# 32-085.net
KiCad netlist of a schematic drawn in Altium Designer
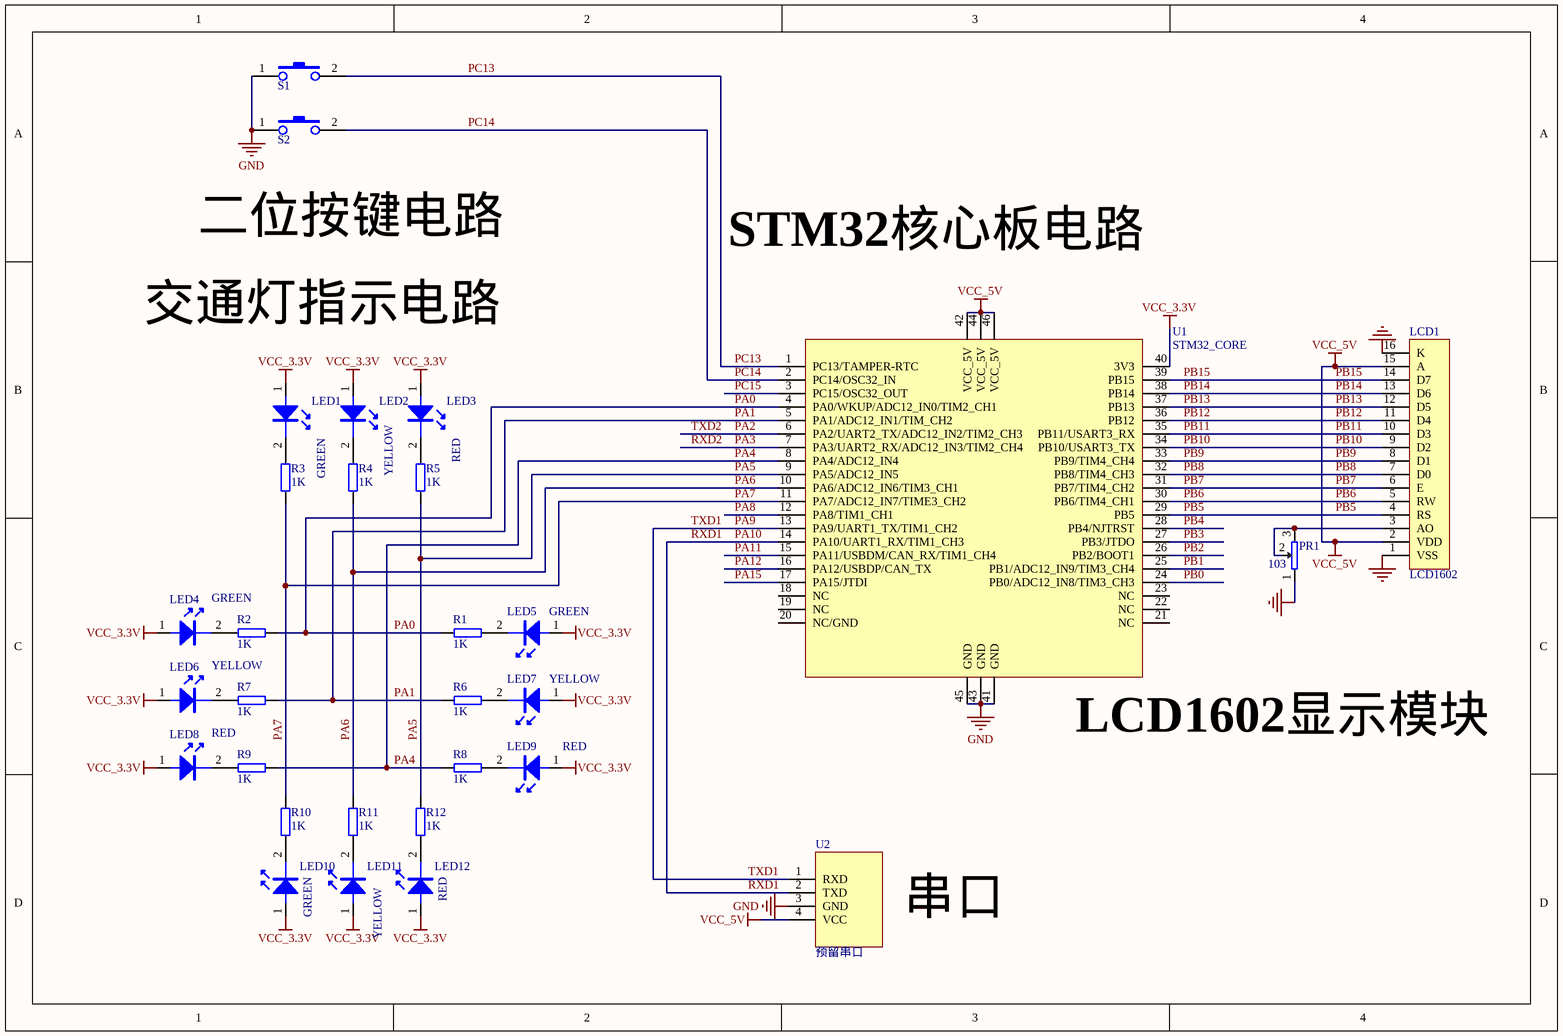
[diagram p0: 32-085原理图（源文件格式）.SchDoc]

(export (version "E")
  (design (tool "Eeschema 10.0.6"))
  (components
    (comp (ref "LCD1")
      (value "LCD1602")
      (footprint "LCD1602")
      (description "LCD1602液晶")
      (libsource (lib "参考") (part "LCD1602"))
    )
    (comp (ref "LED1")
      (value "GREEN")
      (footprint "LED_D3MM12")
      (description "LED灯")
      (libsource (lib "参考") (part "LED"))
    )
    (comp (ref "LED2")
      (value "YELLOW")
      (footprint "LED_D3MM12")
      (description "LED灯")
      (libsource (lib "参考") (part "LED"))
    )
    (comp (ref "LED3")
      (value "RED")
      (footprint "LED_D3MM12")
      (description "LED灯")
      (libsource (lib "参考") (part "LED"))
    )
    (comp (ref "LED4")
      (value "GREEN")
      (footprint "LED_D3MM12")
      (description "LED灯")
      (libsource (lib "参考") (part "LED"))
    )
    (comp (ref "LED5")
      (value "GREEN")
      (footprint "LED_D3MM12")
      (description "LED灯")
      (libsource (lib "参考") (part "LED"))
    )
    (comp (ref "LED6")
      (value "YELLOW")
      (footprint "LED_D3MM12")
      (description "LED灯")
      (libsource (lib "参考") (part "LED"))
    )
    (comp (ref "LED7")
      (value "YELLOW")
      (footprint "LED_D3MM12")
      (description "LED灯")
      (libsource (lib "参考") (part "LED"))
    )
    (comp (ref "LED8")
      (value "RED")
      (footprint "LED_D3MM12")
      (description "LED灯")
      (libsource (lib "参考") (part "LED"))
    )
    (comp (ref "LED9")
      (value "RED")
      (footprint "LED_D3MM12")
      (description "LED灯")
      (libsource (lib "参考") (part "LED"))
    )
    (comp (ref "LED10")
      (value "GREEN")
      (footprint "LED_D3MM12")
      (description "LED灯")
      (libsource (lib "参考") (part "LED"))
    )
    (comp (ref "LED11")
      (value "YELLOW")
      (footprint "LED_D3MM12")
      (description "LED灯")
      (libsource (lib "参考") (part "LED"))
    )
    (comp (ref "LED12")
      (value "RED")
      (footprint "LED_D3MM12")
      (description "LED灯")
      (libsource (lib "参考") (part "LED"))
    )
    (comp (ref "PR1")
      (value "103")
      (footprint "WH06-2")
      (description "电位器")
      (libsource (lib "参考") (part "PR"))
    )
    (comp (ref "R1")
      (value "1K")
      (footprint "AXIAL0.4")
      (description "电阻")
      (libsource (lib "参考") (part "RES"))
    )
    (comp (ref "R2")
      (value "1K")
      (footprint "AXIAL0.3")
      (description "电阻")
      (libsource (lib "参考") (part "RES"))
    )
    (comp (ref "R3")
      (value "1K")
      (footprint "AXIAL0.3")
      (description "电阻")
      (libsource (lib "参考") (part "RES"))
    )
    (comp (ref "R4")
      (value "1K")
      (footprint "AXIAL0.3")
      (description "电阻")
      (libsource (lib "参考") (part "RES"))
    )
    (comp (ref "R5")
      (value "1K")
      (footprint "AXIAL0.3")
      (description "电阻")
      (libsource (lib "参考") (part "RES"))
    )
    (comp (ref "R6")
      (value "1K")
      (footprint "AXIAL0.4")
      (description "电阻")
      (libsource (lib "参考") (part "RES"))
    )
    (comp (ref "R7")
      (value "1K")
      (footprint "AXIAL0.3")
      (description "电阻")
      (libsource (lib "参考") (part "RES"))
    )
    (comp (ref "R8")
      (value "1K")
      (footprint "AXIAL0.4")
      (description "电阻")
      (libsource (lib "参考") (part "RES"))
    )
    (comp (ref "R9")
      (value "1K")
      (footprint "AXIAL0.3")
      (description "电阻")
      (libsource (lib "参考") (part "RES"))
    )
    (comp (ref "R10")
      (value "1K")
      (footprint "AXIAL0.3")
      (description "电阻")
      (libsource (lib "参考") (part "RES"))
    )
    (comp (ref "R11")
      (value "1K")
      (footprint "AXIAL0.3")
      (description "电阻")
      (libsource (lib "参考") (part "RES"))
    )
    (comp (ref "R12")
      (value "1K")
      (footprint "AXIAL0.3")
      (description "电阻")
      (libsource (lib "参考") (part "RES"))
    )
    (comp (ref "S1")
      (value "BUTTOM")
      (footprint "BUTTOM_6x6DIP")
      (description "按键")
      (libsource (lib "参考") (part "BUTTOM"))
    )
    (comp (ref "S2")
      (value "BUTTOM")
      (footprint "BUTTOM_6x6DIP")
      (description "按键")
      (libsource (lib "参考") (part "BUTTOM"))
    )
    (comp (ref "U1")
      (value "STM32_CORE")
      (footprint "STM32_CORE")
      (description "STM32核心板")
      (libsource (lib "参考") (part "STM32_CORE"))
    )
    (comp (ref "U2") (value "预留串口") (footprint "蓝牙MODE竖放") (libsource (lib "参考") (part "蓝牙MODE")))
  )
  (nets
    (net (code "1") (name "/PA0") (class "Default")
      (node (ref "R1") (pin "1") (pinfunction "1_1") (pintype "passive"))
      (node (ref "R2") (pin "1") (pinfunction "1_1") (pintype "passive"))
      (node (ref "U1") (pin "4") (pinfunction "PA0/WKUP/ADC12_IN0/TIM2_CH1_4") (pintype "passive"))
    )
    (net (code "2") (name "/PA1") (class "Default")
      (node (ref "R6") (pin "1") (pinfunction "1_1") (pintype "passive"))
      (node (ref "R7") (pin "1") (pinfunction "1_1") (pintype "passive"))
      (node (ref "U1") (pin "5") (pinfunction "PA1/ADC12_IN1/TIM_CH2_5") (pintype "passive"))
    )
    (net (code "3") (name "/PA2") (class "Default")
      (node (ref "U1") (pin "6") (pinfunction "PA2/UART2_TX/ADC12_IN2/TIM2_CH3_6") (pintype "passive"))
    )
    (net (code "4") (name "/PA3") (class "Default")
      (node (ref "U1") (pin "7") (pinfunction "PA3/UART2_RX/ADC12_IN3/TIM2_CH4_7") (pintype "passive"))
    )
    (net (code "5") (name "/PA4") (class "Default")
      (node (ref "R8") (pin "1") (pinfunction "1_1") (pintype "passive"))
      (node (ref "R9") (pin "1") (pinfunction "1_1") (pintype "passive"))
      (node (ref "U1") (pin "8") (pinfunction "PA4/ADC12_IN4_8") (pintype "passive"))
    )
    (net (code "6") (name "/PA5") (class "Default")
      (node (ref "R12") (pin "1") (pinfunction "1_1") (pintype "passive"))
      (node (ref "R5") (pin "1") (pinfunction "1_1") (pintype "passive"))
      (node (ref "U1") (pin "9") (pinfunction "PA5/ADC12_IN5_9") (pintype "passive"))
    )
    (net (code "7") (name "/PA6") (class "Default")
      (node (ref "R11") (pin "1") (pinfunction "1_1") (pintype "passive"))
      (node (ref "R4") (pin "1") (pinfunction "1_1") (pintype "passive"))
      (node (ref "U1") (pin "10") (pinfunction "PA6/ADC12_IN6/TIM3_CH1_10") (pintype "passive"))
    )
    (net (code "8") (name "/PA7") (class "Default")
      (node (ref "R10") (pin "1") (pinfunction "1_1") (pintype "passive"))
      (node (ref "R3") (pin "1") (pinfunction "1_1") (pintype "passive"))
      (node (ref "U1") (pin "11") (pinfunction "PA7/ADC12_IN7/TIME3_CH2_11") (pintype "passive"))
    )
    (net (code "9") (name "/PA8") (class "Default")
      (node (ref "U1") (pin "12") (pinfunction "PA8/TIM1_CH1_12") (pintype "passive"))
    )
    (net (code "10") (name "/PA9") (class "Default")
      (node (ref "U1") (pin "13") (pinfunction "PA9/UART1_TX/TIM1_CH2_13") (pintype "passive"))
      (node (ref "U2") (pin "1") (pinfunction "RXD_1") (pintype "passive"))
    )
    (net (code "11") (name "/PA10") (class "Default")
      (node (ref "U1") (pin "14") (pinfunction "PA10/UART1_RX/TIM1_CH3_14") (pintype "passive"))
      (node (ref "U2") (pin "2") (pinfunction "TXD_2") (pintype "passive"))
    )
    (net (code "12") (name "/PA11") (class "Default")
      (node (ref "U1") (pin "15") (pinfunction "PA11/USBDM/CAN_RX/TIM1_CH4_15") (pintype "passive"))
    )
    (net (code "13") (name "/PA12") (class "Default")
      (node (ref "U1") (pin "16") (pinfunction "PA12/USBDP/CAN_TX_16") (pintype "passive"))
    )
    (net (code "14") (name "/PA15") (class "Default")
      (node (ref "U1") (pin "17") (pinfunction "PA15/JTDI_17") (pintype "passive"))
    )
    (net (code "15") (name "/PB0") (class "Default")
      (node (ref "U1") (pin "24") (pinfunction "PB0/ADC12_IN8/TIM3_CH3_24") (pintype "passive"))
    )
    (net (code "16") (name "/PB1") (class "Default")
      (node (ref "U1") (pin "25") (pinfunction "PB1/ADC12_IN9/TIM3_CH4_25") (pintype "passive"))
    )
    (net (code "17") (name "/PB2") (class "Default")
      (node (ref "U1") (pin "26") (pinfunction "PB2/BOOT1_26") (pintype "passive"))
    )
    (net (code "18") (name "/PB3") (class "Default")
      (node (ref "U1") (pin "27") (pinfunction "PB3/JTDO_27") (pintype "passive"))
    )
    (net (code "19") (name "/PB4") (class "Default")
      (node (ref "U1") (pin "28") (pinfunction "PB4/NJTRST_28") (pintype "passive"))
    )
    (net (code "20") (name "/PB5") (class "Default")
      (node (ref "LCD1") (pin "4") (pinfunction "RS_4") (pintype "passive"))
      (node (ref "U1") (pin "29") (pinfunction "PB5_29") (pintype "passive"))
    )
    (net (code "21") (name "/PB6") (class "Default")
      (node (ref "LCD1") (pin "5") (pinfunction "RW_5") (pintype "passive"))
      (node (ref "U1") (pin "30") (pinfunction "PB6/TIM4_CH1_30") (pintype "passive"))
    )
    (net (code "22") (name "/PB7") (class "Default")
      (node (ref "LCD1") (pin "6") (pinfunction "E_6") (pintype "passive"))
      (node (ref "U1") (pin "31") (pinfunction "PB7/TIM4_CH2_31") (pintype "passive"))
    )
    (net (code "23") (name "/PB8") (class "Default")
      (node (ref "LCD1") (pin "7") (pinfunction "D0_7") (pintype "passive"))
      (node (ref "U1") (pin "32") (pinfunction "PB8/TIM4_CH3_32") (pintype "passive"))
    )
    (net (code "24") (name "/PB9") (class "Default")
      (node (ref "LCD1") (pin "8") (pinfunction "D1_8") (pintype "passive"))
      (node (ref "U1") (pin "33") (pinfunction "PB9/TIM4_CH4_33") (pintype "passive"))
    )
    (net (code "25") (name "/PB10") (class "Default")
      (node (ref "LCD1") (pin "9") (pinfunction "D2_9") (pintype "passive"))
      (node (ref "U1") (pin "34") (pinfunction "PB10/USART3_TX_34") (pintype "passive"))
    )
    (net (code "26") (name "/PB11") (class "Default")
      (node (ref "LCD1") (pin "10") (pinfunction "D3_10") (pintype "passive"))
      (node (ref "U1") (pin "35") (pinfunction "PB11/USART3_RX_35") (pintype "passive"))
    )
    (net (code "27") (name "/PB12") (class "Default")
      (node (ref "LCD1") (pin "11") (pinfunction "D4_11") (pintype "passive"))
      (node (ref "U1") (pin "36") (pinfunction "PB12_36") (pintype "passive"))
    )
    (net (code "28") (name "/PB13") (class "Default")
      (node (ref "LCD1") (pin "12") (pinfunction "D5_12") (pintype "passive"))
      (node (ref "U1") (pin "37") (pinfunction "PB13_37") (pintype "passive"))
    )
    (net (code "29") (name "/PB14") (class "Default")
      (node (ref "LCD1") (pin "13") (pinfunction "D6_13") (pintype "passive"))
      (node (ref "U1") (pin "38") (pinfunction "PB14_38") (pintype "passive"))
    )
    (net (code "30") (name "/PB15") (class "Default")
      (node (ref "LCD1") (pin "14") (pinfunction "D7_14") (pintype "passive"))
      (node (ref "U1") (pin "39") (pinfunction "PB15_39") (pintype "passive"))
    )
    (net (code "31") (name "/PC13") (class "Default")
      (node (ref "S1") (pin "2") (pinfunction "2_2") (pintype "passive"))
      (node (ref "U1") (pin "1") (pinfunction "PC13/TAMPER-RTC_1") (pintype "passive"))
    )
    (net (code "32") (name "/PC14") (class "Default")
      (node (ref "S2") (pin "2") (pinfunction "2_2") (pintype "passive"))
      (node (ref "U1") (pin "2") (pinfunction "PC14/OSC32_IN_2") (pintype "passive"))
    )
    (net (code "33") (name "/PC15") (class "Default")
      (node (ref "U1") (pin "3") (pinfunction "PC15/OSC32_OUT_3") (pintype "passive"))
    )
    (net (code "34") (name "GND") (class "Default")
      (node (ref "LCD1") (pin "1") (pinfunction "VSS_1") (pintype "passive"))
      (node (ref "LCD1") (pin "16") (pinfunction "K_16") (pintype "passive"))
      (node (ref "PR1") (pin "1") (pinfunction "1_1") (pintype "passive"))
      (node (ref "S1") (pin "1") (pinfunction "1_1") (pintype "passive"))
      (node (ref "S2") (pin "1") (pinfunction "1_1") (pintype "passive"))
      (node (ref "U1") (pin "41") (pinfunction "GND_41") (pintype "passive"))
      (node (ref "U1") (pin "43") (pinfunction "GND_43") (pintype "passive"))
      (node (ref "U1") (pin "45") (pinfunction "GND_45") (pintype "passive"))
      (node (ref "U2") (pin "3") (pinfunction "GND_3") (pintype "passive"))
    )
    (net (code "35") (name "Net-(LCD1-AO)") (class "Default")
      (node (ref "LCD1") (pin "3") (pinfunction "AO_3") (pintype "passive"))
      (node (ref "PR1") (pin "2") (pinfunction "2_2") (pintype "passive"))
      (node (ref "PR1") (pin "3") (pinfunction "3_3") (pintype "passive"))
    )
    (net (code "36") (name "Net-(LED1-Pad2)") (class "Default")
      (node (ref "LED1") (pin "2") (pinfunction "2_2") (pintype "passive"))
      (node (ref "R3") (pin "2") (pinfunction "2_2") (pintype "passive"))
    )
    (net (code "37") (name "Net-(LED2-Pad2)") (class "Default")
      (node (ref "LED2") (pin "2") (pinfunction "2_2") (pintype "passive"))
      (node (ref "R4") (pin "2") (pinfunction "2_2") (pintype "passive"))
    )
    (net (code "38") (name "Net-(LED3-Pad2)") (class "Default")
      (node (ref "LED3") (pin "2") (pinfunction "2_2") (pintype "passive"))
      (node (ref "R5") (pin "2") (pinfunction "2_2") (pintype "passive"))
    )
    (net (code "39") (name "Net-(LED4-Pad2)") (class "Default")
      (node (ref "LED4") (pin "2") (pinfunction "2_2") (pintype "passive"))
      (node (ref "R2") (pin "2") (pinfunction "2_2") (pintype "passive"))
    )
    (net (code "40") (name "Net-(LED5-Pad2)") (class "Default")
      (node (ref "LED5") (pin "2") (pinfunction "2_2") (pintype "passive"))
      (node (ref "R1") (pin "2") (pinfunction "2_2") (pintype "passive"))
    )
    (net (code "41") (name "Net-(LED6-Pad2)") (class "Default")
      (node (ref "LED6") (pin "2") (pinfunction "2_2") (pintype "passive"))
      (node (ref "R7") (pin "2") (pinfunction "2_2") (pintype "passive"))
    )
    (net (code "42") (name "Net-(LED7-Pad2)") (class "Default")
      (node (ref "LED7") (pin "2") (pinfunction "2_2") (pintype "passive"))
      (node (ref "R6") (pin "2") (pinfunction "2_2") (pintype "passive"))
    )
    (net (code "43") (name "Net-(LED8-Pad2)") (class "Default")
      (node (ref "LED8") (pin "2") (pinfunction "2_2") (pintype "passive"))
      (node (ref "R9") (pin "2") (pinfunction "2_2") (pintype "passive"))
    )
    (net (code "44") (name "Net-(LED9-Pad2)") (class "Default")
      (node (ref "LED9") (pin "2") (pinfunction "2_2") (pintype "passive"))
      (node (ref "R8") (pin "2") (pinfunction "2_2") (pintype "passive"))
    )
    (net (code "45") (name "Net-(LED10-Pad2)") (class "Default")
      (node (ref "LED10") (pin "2") (pinfunction "2_2") (pintype "passive"))
      (node (ref "R10") (pin "2") (pinfunction "2_2") (pintype "passive"))
    )
    (net (code "46") (name "Net-(LED11-Pad2)") (class "Default")
      (node (ref "LED11") (pin "2") (pinfunction "2_2") (pintype "passive"))
      (node (ref "R11") (pin "2") (pinfunction "2_2") (pintype "passive"))
    )
    (net (code "47") (name "Net-(LED12-Pad2)") (class "Default")
      (node (ref "LED12") (pin "2") (pinfunction "2_2") (pintype "passive"))
      (node (ref "R12") (pin "2") (pinfunction "2_2") (pintype "passive"))
    )
    (net (code "48") (name "VCC_3.3V") (class "Default")
      (node (ref "LED1") (pin "1") (pinfunction "1_1") (pintype "passive"))
      (node (ref "LED10") (pin "1") (pinfunction "1_1") (pintype "passive"))
      (node (ref "LED11") (pin "1") (pinfunction "1_1") (pintype "passive"))
      (node (ref "LED12") (pin "1") (pinfunction "1_1") (pintype "passive"))
      (node (ref "LED2") (pin "1") (pinfunction "1_1") (pintype "passive"))
      (node (ref "LED3") (pin "1") (pinfunction "1_1") (pintype "passive"))
      (node (ref "LED4") (pin "1") (pinfunction "1_1") (pintype "passive"))
      (node (ref "LED5") (pin "1") (pinfunction "1_1") (pintype "passive"))
      (node (ref "LED6") (pin "1") (pinfunction "1_1") (pintype "passive"))
      (node (ref "LED7") (pin "1") (pinfunction "1_1") (pintype "passive"))
      (node (ref "LED8") (pin "1") (pinfunction "1_1") (pintype "passive"))
      (node (ref "LED9") (pin "1") (pinfunction "1_1") (pintype "passive"))
      (node (ref "U1") (pin "40") (pinfunction "3V3_40") (pintype "passive"))
    )
    (net (code "49") (name "VCC_5V") (class "Default")
      (node (ref "LCD1") (pin "15") (pinfunction "A_15") (pintype "passive"))
      (node (ref "LCD1") (pin "2") (pinfunction "VDD_2") (pintype "passive"))
      (node (ref "U1") (pin "42") (pinfunction "VCC_5V_42") (pintype "passive"))
      (node (ref "U1") (pin "44") (pinfunction "VCC_5V_44") (pintype "passive"))
      (node (ref "U1") (pin "46") (pinfunction "VCC_5V_46") (pintype "passive"))
      (node (ref "U2") (pin "4") (pinfunction "VCC_4") (pintype "passive"))
    )
    (net (code "50") (name "unconnected-(U1-NC-Pad18)") (class "Default")
      (node (ref "U1") (pin "18") (pinfunction "NC_18") (pintype "passive"))
    )
    (net (code "51") (name "unconnected-(U1-NC-Pad19)") (class "Default")
      (node (ref "U1") (pin "19") (pinfunction "NC_19") (pintype "passive"))
    )
    (net (code "52") (name "unconnected-(U1-NC-Pad21)") (class "Default")
      (node (ref "U1") (pin "21") (pinfunction "NC_21") (pintype "passive"))
    )
    (net (code "53") (name "unconnected-(U1-NC-Pad22)") (class "Default")
      (node (ref "U1") (pin "22") (pinfunction "NC_22") (pintype "passive"))
    )
    (net (code "54") (name "unconnected-(U1-NC-Pad23)") (class "Default")
      (node (ref "U1") (pin "23") (pinfunction "NC_23") (pintype "passive"))
    )
    (net (code "55") (name "unconnected-(U1-NC{slash}GND-Pad20)") (class "Default")
      (node (ref "U1") (pin "20") (pinfunction "NC/GND_20") (pintype "passive"))
    )
  )
)
